# 04_4G.net
KiCad netlist of a schematic drawn in Altium Designer
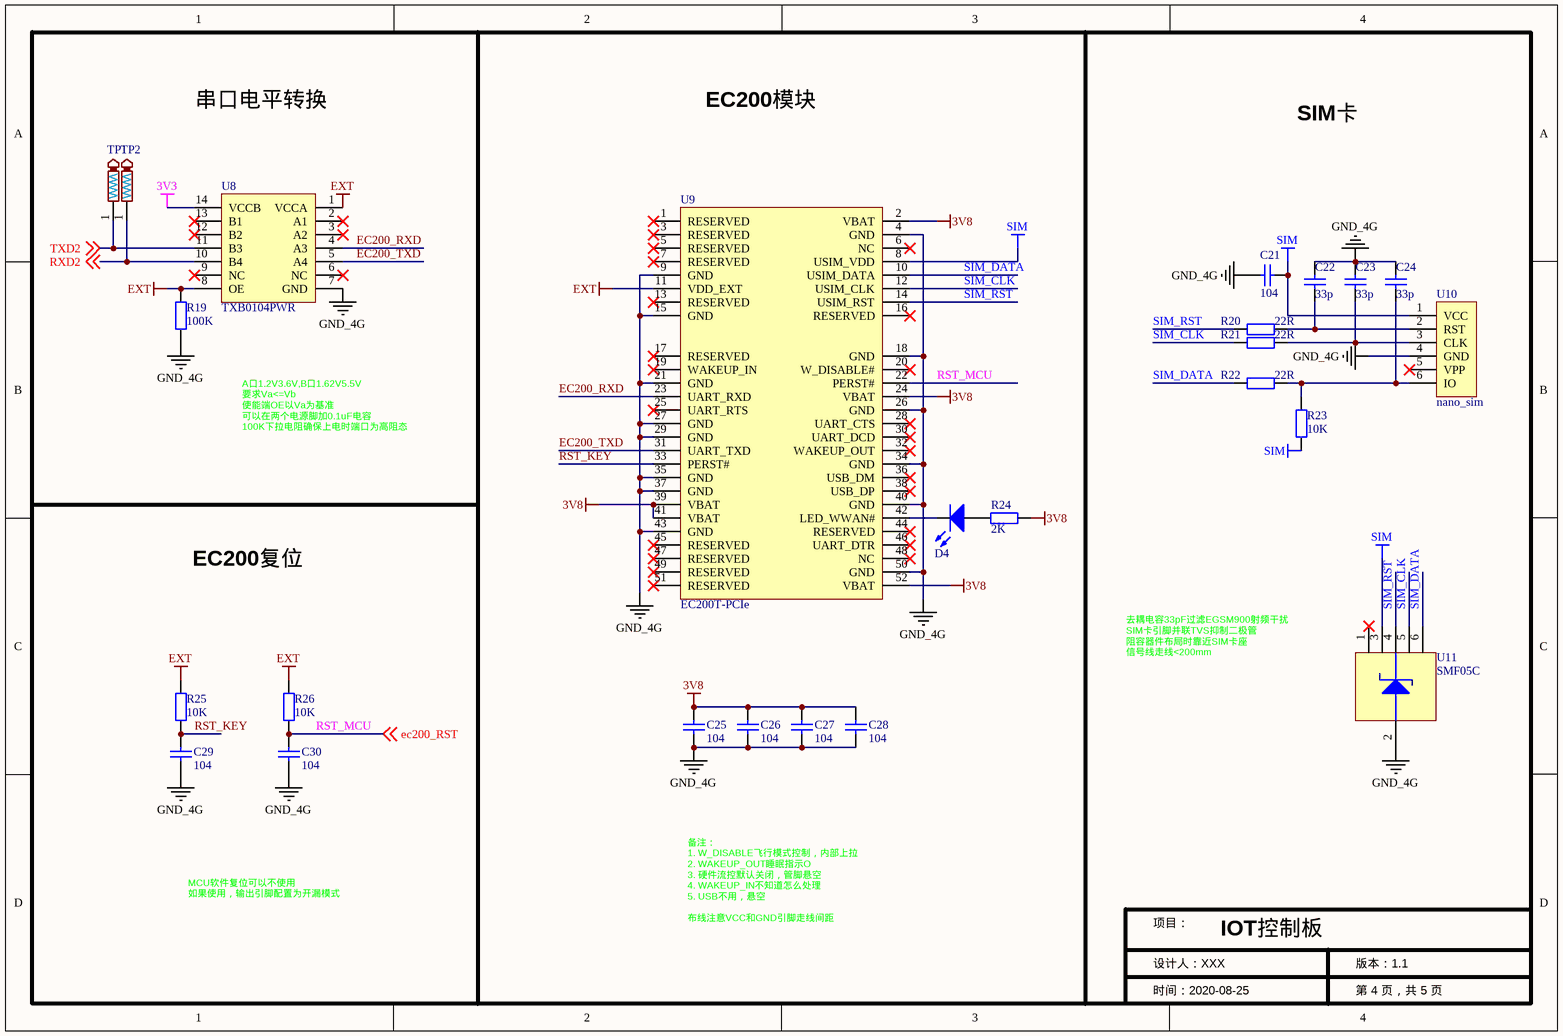
[diagram p0: 04_4G模块和外围电路.SchDoc]

(export (version "E")
  (design (tool "Eeschema 10.0.6"))
  (components
    (comp (ref "C21")
      (value "104")
      (footprint "CAP-0603")
      (description "无极性电容")
      (fields (field (name "Comment") "Cap") (field (name "PUBLISHER") "Altium Limited"))
      (libsource (lib "Arrowy_Racing") (part "Cap"))
    )
    (comp (ref "C22")
      (value "33p")
      (footprint "CAP-0603")
      (description "无极性电容")
      (fields (field (name "Comment") "Cap") (field (name "PUBLISHER") "Altium Limited"))
      (libsource (lib "Arrowy_Racing") (part "Cap"))
    )
    (comp (ref "C23")
      (value "33p")
      (footprint "CAP-0603")
      (description "无极性电容")
      (fields (field (name "Comment") "Cap") (field (name "PUBLISHER") "Altium Limited"))
      (libsource (lib "Arrowy_Racing") (part "Cap"))
    )
    (comp (ref "C24")
      (value "33p")
      (footprint "CAP-0603")
      (description "无极性电容")
      (fields (field (name "Comment") "Cap") (field (name "PUBLISHER") "Altium Limited"))
      (libsource (lib "Arrowy_Racing") (part "Cap"))
    )
    (comp (ref "C25")
      (value "104")
      (footprint "CAP-0603")
      (description "无极性电容")
      (fields (field (name "Comment") "Cap") (field (name "PUBLISHER") "Altium Limited"))
      (libsource (lib "Arrowy_Racing") (part "Cap"))
    )
    (comp (ref "C26")
      (value "104")
      (footprint "CAP-0603")
      (description "无极性电容")
      (fields (field (name "Comment") "Cap") (field (name "PUBLISHER") "Altium Limited"))
      (libsource (lib "Arrowy_Racing") (part "Cap"))
    )
    (comp (ref "C27")
      (value "104")
      (footprint "CAP-0603")
      (description "无极性电容")
      (fields (field (name "Comment") "Cap") (field (name "PUBLISHER") "Altium Limited"))
      (libsource (lib "Arrowy_Racing") (part "Cap"))
    )
    (comp (ref "C28")
      (value "104")
      (footprint "CAP-0603")
      (description "无极性电容")
      (fields (field (name "Comment") "Cap") (field (name "PUBLISHER") "Altium Limited"))
      (libsource (lib "Arrowy_Racing") (part "Cap"))
    )
    (comp (ref "C29")
      (value "104")
      (footprint "CAP-0603")
      (description "无极性电容")
      (fields (field (name "Comment") "Cap") (field (name "PUBLISHER") "Altium Limited"))
      (libsource (lib "Arrowy_Racing") (part "Cap"))
    )
    (comp (ref "C30")
      (value "104")
      (footprint "CAP-0603")
      (description "无极性电容")
      (fields (field (name "Comment") "Cap") (field (name "PUBLISHER") "Altium Limited"))
      (libsource (lib "Arrowy_Racing") (part "Cap"))
    )
    (comp (ref "D4")
      (value "LED")
      (footprint "LED_0805")
      (description "发光二极管")
      (fields (field (name "PUBLISHER") "Altium Limited"))
      (libsource (lib "Arrowy_Racing") (part "LED"))
    )
    (comp (ref "R19")
      (value "100K")
      (footprint "0603")
      (description "贴片电阻")
      (fields (field (name "Comment") "Res") (field (name "PUBLISHER") "Altium Limited"))
      (libsource (lib "") (part "Res_2"))
    )
    (comp (ref "R20")
      (value "22R")
      (footprint "0603")
      (description "贴片电阻")
      (fields (field (name "Comment") "Res") (field (name "PUBLISHER") "Altium Limited"))
      (libsource (lib "") (part "Res_2"))
    )
    (comp (ref "R21")
      (value "22R")
      (footprint "0603")
      (description "贴片电阻")
      (fields (field (name "Comment") "Res") (field (name "PUBLISHER") "Altium Limited"))
      (libsource (lib "") (part "Res_2"))
    )
    (comp (ref "R22")
      (value "22R")
      (footprint "0603")
      (description "贴片电阻")
      (fields (field (name "Comment") "Res") (field (name "PUBLISHER") "Altium Limited"))
      (libsource (lib "") (part "Res_2"))
    )
    (comp (ref "R23")
      (value "10K")
      (footprint "0603")
      (description "贴片电阻")
      (fields (field (name "Comment") "Res") (field (name "PUBLISHER") "Altium Limited"))
      (libsource (lib "") (part "Res_1"))
    )
    (comp (ref "R24")
      (value "2K")
      (footprint "0603")
      (description "贴片电阻")
      (fields (field (name "Comment") "Res") (field (name "PUBLISHER") "Altium Limited"))
      (libsource (lib "Arrowy_Racing") (part "Res"))
    )
    (comp (ref "R25")
      (value "10K")
      (footprint "0603")
      (description "贴片电阻")
      (fields (field (name "Comment") "Res") (field (name "PUBLISHER") "Altium Limited"))
      (libsource (lib "") (part "Res_3"))
    )
    (comp (ref "R26")
      (value "10K")
      (footprint "0603")
      (description "贴片电阻")
      (fields (field (name "Comment") "Res") (field (name "PUBLISHER") "Altium Limited"))
      (libsource (lib "") (part "Res_1"))
    )
    (comp (ref "TP1")
      (value "TestPoint")
      (footprint "TESTPOINT")
      (description "测试点")
      (libsource (lib "Arrowy_Racing") (part "TestPoint"))
    )
    (comp (ref "TP2")
      (value "TestPoint")
      (footprint "TESTPOINT")
      (description "测试点")
      (libsource (lib "Arrowy_Racing") (part "TestPoint"))
    )
    (comp (ref "U8")
      (value "TXB0104PWR")
      (footprint "TSSOP-14")
      (description "电平转换芯片")
      (libsource (lib "Arrowy_Racing") (part "TXB0104PWR"))
    )
    (comp (ref "U9")
      (value "EC200T-PCIe")
      (footprint "miniPCIe1")
      (libsource (lib "Arrowy_Racing") (part "EC200T-PCIe"))
    )
    (comp (ref "U10")
      (value "nano_sim")
      (footprint "Nano_SIM_6P")
      (libsource (lib "Arrowy_Racing") (part "nano_sim"))
    )
    (comp (ref "U11")
      (value "SMF05C")
      (footprint "SOT-363")
      (libsource (lib "Arrowy_Racing") (part "SMF05C"))
    )
  )
  (nets
    (net (code "1") (name "/EC200_RXD") (class "Default")
      (node (ref "U8") (pin "4") (pinfunction "A3_4") (pintype "passive"))
      (node (ref "U9") (pin "23") (pinfunction "UART_RXD_23") (pintype "passive"))
    )
    (net (code "2") (name "/EC200_TXD") (class "Default")
      (node (ref "U8") (pin "5") (pinfunction "A4_5") (pintype "passive"))
      (node (ref "U9") (pin "31") (pinfunction "UART_TXD_31") (pintype "passive"))
    )
    (net (code "3") (name "/RST_KEY") (class "Default")
      (node (ref "C29") (pin "2") (pinfunction "2_2") (pintype "passive"))
      (node (ref "R25") (pin "1") (pinfunction "1_1") (pintype "passive"))
      (node (ref "U9") (pin "33") (pinfunction "PERST#_33") (pintype "passive"))
    )
    (net (code "4") (name "/SIM_CLK") (class "Default")
      (node (ref "R21") (pin "1") (pinfunction "1_1") (pintype "passive"))
      (node (ref "U11") (pin "5") (pinfunction "gnd_5") (pintype "passive"))
      (node (ref "U9") (pin "12") (pinfunction "USIM_CLK_12") (pintype "passive"))
    )
    (net (code "5") (name "/SIM_DATA") (class "Default")
      (node (ref "R22") (pin "1") (pinfunction "1_1") (pintype "passive"))
      (node (ref "U11") (pin "6") (pinfunction "gnd_6") (pintype "passive"))
      (node (ref "U9") (pin "10") (pinfunction "USIM_DATA_10") (pintype "passive"))
    )
    (net (code "6") (name "/SIM_RST") (class "Default")
      (node (ref "R20") (pin "1") (pinfunction "1_1") (pintype "passive"))
      (node (ref "U11") (pin "4") (pinfunction "gnd_4") (pintype "passive"))
      (node (ref "U9") (pin "14") (pinfunction "USIM_RST_14") (pintype "passive"))
    )
    (net (code "7") (name "3V3") (class "Default")
      (node (ref "U8") (pin "14") (pinfunction "VCCB_14") (pintype "passive"))
    )
    (net (code "8") (name "3V8") (class "Default")
      (node (ref "C25") (pin "2") (pinfunction "2_2") (pintype "passive"))
      (node (ref "C26") (pin "2") (pinfunction "2_2") (pintype "passive"))
      (node (ref "C27") (pin "2") (pinfunction "2_2") (pintype "passive"))
      (node (ref "C28") (pin "2") (pinfunction "2_2") (pintype "passive"))
      (node (ref "R24") (pin "1") (pinfunction "1_1") (pintype "passive"))
      (node (ref "U9") (pin "2") (pinfunction "VBAT_2") (pintype "passive"))
      (node (ref "U9") (pin "24") (pinfunction "VBAT_24") (pintype "passive"))
      (node (ref "U9") (pin "39") (pinfunction "VBAT_39") (pintype "passive"))
      (node (ref "U9") (pin "41") (pinfunction "VBAT_41") (pintype "passive"))
      (node (ref "U9") (pin "52") (pinfunction "VBAT_52") (pintype "passive"))
    )
    (net (code "9") (name "EXT") (class "Default")
      (node (ref "R19") (pin "2") (pinfunction "2_2") (pintype "passive"))
      (node (ref "R25") (pin "2") (pinfunction "2_2") (pintype "passive"))
      (node (ref "R26") (pin "1") (pinfunction "1_1") (pintype "passive"))
      (node (ref "U8") (pin "1") (pinfunction "VCCA_1") (pintype "passive"))
      (node (ref "U8") (pin "8") (pinfunction "OE_8") (pintype "passive"))
      (node (ref "U9") (pin "11") (pinfunction "VDD_EXT_11") (pintype "passive"))
    )
    (net (code "10") (name "GND_4G") (class "Default")
      (node (ref "C21") (pin "2") (pinfunction "2_2") (pintype "passive"))
      (node (ref "C22") (pin "1") (pinfunction "1_1") (pintype "passive"))
      (node (ref "C23") (pin "1") (pinfunction "1_1") (pintype "passive"))
      (node (ref "C24") (pin "2") (pinfunction "2_2") (pintype "passive"))
      (node (ref "C25") (pin "1") (pinfunction "1_1") (pintype "passive"))
      (node (ref "C26") (pin "1") (pinfunction "1_1") (pintype "passive"))
      (node (ref "C27") (pin "1") (pinfunction "1_1") (pintype "passive"))
      (node (ref "C28") (pin "1") (pinfunction "1_1") (pintype "passive"))
      (node (ref "C29") (pin "1") (pinfunction "1_1") (pintype "passive"))
      (node (ref "C30") (pin "2") (pinfunction "2_2") (pintype "passive"))
      (node (ref "R19") (pin "1") (pinfunction "1_1") (pintype "passive"))
      (node (ref "U10") (pin "4") (pinfunction "GND_4") (pintype "passive"))
      (node (ref "U11") (pin "2") (pinfunction "gnd_2") (pintype "passive"))
      (node (ref "U8") (pin "7") (pinfunction "GND_7") (pintype "passive"))
      (node (ref "U9") (pin "15") (pinfunction "GND_15") (pintype "passive"))
      (node (ref "U9") (pin "18") (pinfunction "GND_18") (pintype "passive"))
      (node (ref "U9") (pin "21") (pinfunction "GND_21") (pintype "passive"))
      (node (ref "U9") (pin "26") (pinfunction "GND_26") (pintype "passive"))
      (node (ref "U9") (pin "27") (pinfunction "GND_27") (pintype "passive"))
      (node (ref "U9") (pin "29") (pinfunction "GND_29") (pintype "passive"))
      (node (ref "U9") (pin "34") (pinfunction "GND_34") (pintype "passive"))
      (node (ref "U9") (pin "35") (pinfunction "GND_35") (pintype "passive"))
      (node (ref "U9") (pin "37") (pinfunction "GND_37") (pintype "passive"))
      (node (ref "U9") (pin "4") (pinfunction "GND_4") (pintype "passive"))
      (node (ref "U9") (pin "40") (pinfunction "GND_40") (pintype "passive"))
      (node (ref "U9") (pin "43") (pinfunction "GND_43") (pintype "passive"))
      (node (ref "U9") (pin "50") (pinfunction "GND_50") (pintype "passive"))
      (node (ref "U9") (pin "9") (pinfunction "GND_9") (pintype "passive"))
    )
    (net (code "11") (name "Net-(D4-A)") (class "Default")
      (node (ref "D4") (pin "1") (pinfunction "A_1") (pintype "passive"))
      (node (ref "R24") (pin "2") (pinfunction "2_2") (pintype "passive"))
    )
    (net (code "12") (name "Net-(D4-K)") (class "Default")
      (node (ref "D4") (pin "2") (pinfunction "K_2") (pintype "passive"))
      (node (ref "U9") (pin "42") (pinfunction "LED_WWAN#_42") (pintype "passive"))
    )
    (net (code "13") (name "Net-(U10-CLK)") (class "Default")
      (node (ref "C23") (pin "2") (pinfunction "2_2") (pintype "passive"))
      (node (ref "R21") (pin "2") (pinfunction "2_2") (pintype "passive"))
      (node (ref "U10") (pin "3") (pinfunction "CLK_3") (pintype "passive"))
    )
    (net (code "14") (name "Net-(U10-IO)") (class "Default")
      (node (ref "C24") (pin "1") (pinfunction "1_1") (pintype "passive"))
      (node (ref "R22") (pin "2") (pinfunction "2_2") (pintype "passive"))
      (node (ref "R23") (pin "1") (pinfunction "1_1") (pintype "passive"))
      (node (ref "U10") (pin "6") (pinfunction "IO_6") (pintype "passive"))
    )
    (net (code "15") (name "Net-(U10-RST)") (class "Default")
      (node (ref "C22") (pin "2") (pinfunction "2_2") (pintype "passive"))
      (node (ref "R20") (pin "2") (pinfunction "2_2") (pintype "passive"))
      (node (ref "U10") (pin "2") (pinfunction "RST_2") (pintype "passive"))
    )
    (net (code "16") (name "RXD2") (class "Default")
      (node (ref "TP2") (pin "1") (pinfunction "OSC_OUT_1") (pintype "passive"))
      (node (ref "U8") (pin "10") (pinfunction "B4_10") (pintype "passive"))
    )
    (net (code "17") (name "SIM") (class "Default")
      (node (ref "C21") (pin "1") (pinfunction "1_1") (pintype "passive"))
      (node (ref "R23") (pin "2") (pinfunction "2_2") (pintype "passive"))
      (node (ref "U10") (pin "1") (pinfunction "VCC_1") (pintype "passive"))
      (node (ref "U11") (pin "3") (pinfunction "gnd_3") (pintype "passive"))
      (node (ref "U9") (pin "8") (pinfunction "USIM_VDD_8") (pintype "passive"))
    )
    (net (code "18") (name "TXD2") (class "Default")
      (node (ref "TP1") (pin "1") (pinfunction "OSC_OUT_1") (pintype "passive"))
      (node (ref "U8") (pin "11") (pinfunction "B3_11") (pintype "passive"))
    )
    (net (code "19") (name "ec200_RST") (class "Default")
      (node (ref "C30") (pin "1") (pinfunction "1_1") (pintype "passive"))
      (node (ref "R26") (pin "2") (pinfunction "2_2") (pintype "passive"))
      (node (ref "U9") (pin "22") (pinfunction "PERST#_22") (pintype "passive"))
    )
    (net (code "20") (name "unconnected-(U8-A1-Pad2)") (class "Default")
      (node (ref "U8") (pin "2") (pinfunction "A1_2") (pintype "passive+no_connect"))
    )
    (net (code "21") (name "unconnected-(U8-A2-Pad3)") (class "Default")
      (node (ref "U8") (pin "3") (pinfunction "A2_3") (pintype "passive+no_connect"))
    )
    (net (code "22") (name "unconnected-(U8-B1-Pad13)") (class "Default")
      (node (ref "U8") (pin "13") (pinfunction "B1_13") (pintype "passive+no_connect"))
    )
    (net (code "23") (name "unconnected-(U8-B2-Pad12)") (class "Default")
      (node (ref "U8") (pin "12") (pinfunction "B2_12") (pintype "passive+no_connect"))
    )
    (net (code "24") (name "unconnected-(U8-NC-Pad6)") (class "Default")
      (node (ref "U8") (pin "6") (pinfunction "NC_6") (pintype "passive+no_connect"))
    )
    (net (code "25") (name "unconnected-(U8-NC-Pad9)") (class "Default")
      (node (ref "U8") (pin "9") (pinfunction "NC_9") (pintype "passive+no_connect"))
    )
    (net (code "26") (name "unconnected-(U9-NC-Pad6)") (class "Default")
      (node (ref "U9") (pin "6") (pinfunction "NC_6") (pintype "passive+no_connect"))
    )
    (net (code "27") (name "unconnected-(U9-NC-Pad48)") (class "Default")
      (node (ref "U9") (pin "48") (pinfunction "NC_48") (pintype "passive+no_connect"))
    )
    (net (code "28") (name "unconnected-(U9-RESERVED-Pad1)") (class "Default")
      (node (ref "U9") (pin "1") (pinfunction "RESERVED_1") (pintype "passive+no_connect"))
    )
    (net (code "29") (name "unconnected-(U9-RESERVED-Pad3)") (class "Default")
      (node (ref "U9") (pin "3") (pinfunction "RESERVED_3") (pintype "passive+no_connect"))
    )
    (net (code "30") (name "unconnected-(U9-RESERVED-Pad5)") (class "Default")
      (node (ref "U9") (pin "5") (pinfunction "RESERVED_5") (pintype "passive+no_connect"))
    )
    (net (code "31") (name "unconnected-(U9-RESERVED-Pad7)") (class "Default")
      (node (ref "U9") (pin "7") (pinfunction "RESERVED_7") (pintype "passive+no_connect"))
    )
    (net (code "32") (name "unconnected-(U9-RESERVED-Pad13)") (class "Default")
      (node (ref "U9") (pin "13") (pinfunction "RESERVED_13") (pintype "passive+no_connect"))
    )
    (net (code "33") (name "unconnected-(U9-RESERVED-Pad16)") (class "Default")
      (node (ref "U9") (pin "16") (pinfunction "RESERVED_16") (pintype "passive+no_connect"))
    )
    (net (code "34") (name "unconnected-(U9-RESERVED-Pad17)") (class "Default")
      (node (ref "U9") (pin "17") (pinfunction "RESERVED_17") (pintype "passive+no_connect"))
    )
    (net (code "35") (name "unconnected-(U9-RESERVED-Pad44)") (class "Default")
      (node (ref "U9") (pin "44") (pinfunction "RESERVED_44") (pintype "passive+no_connect"))
    )
    (net (code "36") (name "unconnected-(U9-RESERVED-Pad45)") (class "Default")
      (node (ref "U9") (pin "45") (pinfunction "RESERVED_45") (pintype "passive+no_connect"))
    )
    (net (code "37") (name "unconnected-(U9-RESERVED-Pad47)") (class "Default")
      (node (ref "U9") (pin "47") (pinfunction "RESERVED_47") (pintype "passive+no_connect"))
    )
    (net (code "38") (name "unconnected-(U9-RESERVED-Pad49)") (class "Default")
      (node (ref "U9") (pin "49") (pinfunction "RESERVED_49") (pintype "passive+no_connect"))
    )
    (net (code "39") (name "unconnected-(U9-RESERVED-Pad51)") (class "Default")
      (node (ref "U9") (pin "51") (pinfunction "RESERVED_51") (pintype "passive+no_connect"))
    )
    (net (code "40") (name "unconnected-(U9-UART_CTS-Pad28)") (class "Default")
      (node (ref "U9") (pin "28") (pinfunction "UART_CTS_28") (pintype "passive+no_connect"))
    )
    (net (code "41") (name "unconnected-(U9-UART_DCD-Pad30)") (class "Default")
      (node (ref "U9") (pin "30") (pinfunction "UART_DCD_30") (pintype "passive+no_connect"))
    )
    (net (code "42") (name "unconnected-(U9-UART_DTR-Pad46)") (class "Default")
      (node (ref "U9") (pin "46") (pinfunction "UART_DTR_46") (pintype "passive+no_connect"))
    )
    (net (code "43") (name "unconnected-(U9-UART_RTS-Pad25)") (class "Default")
      (node (ref "U9") (pin "25") (pinfunction "UART_RTS_25") (pintype "passive+no_connect"))
    )
    (net (code "44") (name "unconnected-(U9-USB_DM-Pad36)") (class "Default")
      (node (ref "U9") (pin "36") (pinfunction "USB_DM_36") (pintype "passive+no_connect"))
    )
    (net (code "45") (name "unconnected-(U9-USB_DP-Pad38)") (class "Default")
      (node (ref "U9") (pin "38") (pinfunction "USB_DP_38") (pintype "passive+no_connect"))
    )
    (net (code "46") (name "unconnected-(U9-WAKEUP_IN-Pad19)") (class "Default")
      (node (ref "U9") (pin "19") (pinfunction "WAKEUP_IN_19") (pintype "passive+no_connect"))
    )
    (net (code "47") (name "unconnected-(U9-WAKEUP_OUT-Pad32)") (class "Default")
      (node (ref "U9") (pin "32") (pinfunction "WAKEUP_OUT_32") (pintype "passive+no_connect"))
    )
    (net (code "48") (name "unconnected-(U9-W_DISABLE#-Pad20)") (class "Default")
      (node (ref "U9") (pin "20") (pinfunction "W_DISABLE#_20") (pintype "passive+no_connect"))
    )
    (net (code "49") (name "unconnected-(U10-VPP-Pad5)") (class "Default")
      (node (ref "U10") (pin "5") (pinfunction "VPP_5") (pintype "passive+no_connect"))
    )
    (net (code "50") (name "unconnected-(U11-gnd-Pad1)") (class "Default")
      (node (ref "U11") (pin "1") (pinfunction "gnd_1") (pintype "passive+no_connect"))
    )
  )
)
